# Part3.net
KiCad netlist of a schematic drawn in Altium Designer
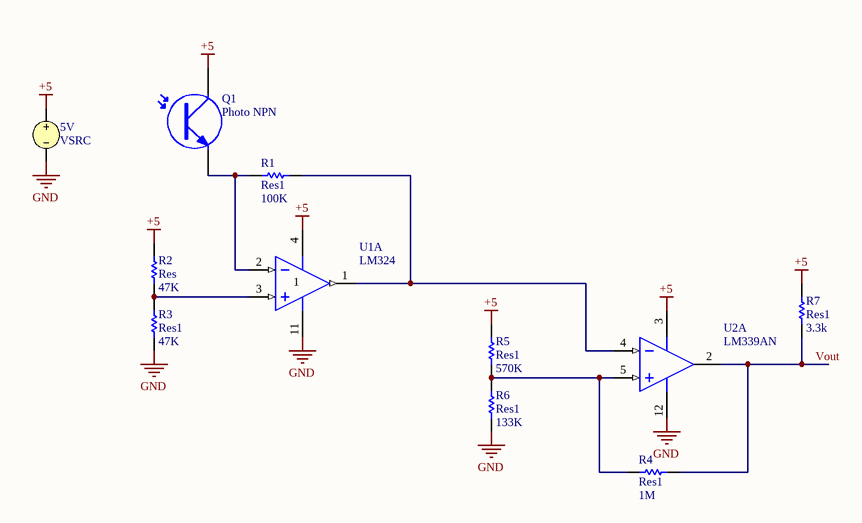
[diagram p0: Part3.SchDoc]

(export (version "E")
  (design (tool "Eeschema 10.0.6"))
  (components
    (comp (ref "5V")
      (value "VSRC")
      (description "Voltage Source")
      (fields (field (name "PUBLISHER") "Altium Limited"))
      (libsource (lib "Simulation Sources") (part "VSRC"))
    )
    (comp (ref "Q1")
      (value "Photo NPN")
      (footprint "SFM-T2(3)/X1.6V")
      (description "NPN Phototransistor")
      (fields (field (name "MANUFACTURER") "Generic Components"))
      (libsource (lib "ME218_BaseLib") (part "Photo NPN"))
    )
    (comp (ref "R1")
      (value "Res1")
      (footprint "AXIAL-0.3")
      (description "Resistor")
      (fields
        (field (name "MANUFACTURER") "Generic Components")
        (field (name "ALTIUM_VALUE") "100K")
        (field (name "PUBLISHER") "Altium Hobart Technology Centre")
      )
      (libsource (lib "ME218_BaseLib") (part "Res1"))
    )
    (comp (ref "R2")
      (value "Res")
      (footprint "AXIAL-0.3")
      (description "Resistor")
      (fields
        (field (name "MANUFACTURER") "Generic Components")
        (field (name "ALTIUM_VALUE") "47K")
        (field (name "PUBLISHER") "Altium Hobart Technology Centre")
      )
      (libsource (lib "ME218_BaseLib") (part "Res1"))
    )
    (comp (ref "R3")
      (value "Res1")
      (footprint "AXIAL-0.3")
      (description "Resistor")
      (fields
        (field (name "MANUFACTURER") "Generic Components")
        (field (name "ALTIUM_VALUE") "47K")
        (field (name "PUBLISHER") "Altium Hobart Technology Centre")
      )
      (libsource (lib "ME218_BaseLib") (part "Res1"))
    )
    (comp (ref "R4")
      (value "Res1")
      (footprint "AXIAL-0.3")
      (description "Resistor")
      (fields
        (field (name "MANUFACTURER") "Generic Components")
        (field (name "ALTIUM_VALUE") "1M")
        (field (name "PUBLISHER") "Altium Hobart Technology Centre")
      )
      (libsource (lib "ME218_BaseLib") (part "Res1"))
    )
    (comp (ref "R5")
      (value "Res1")
      (footprint "AXIAL-0.3")
      (description "Resistor")
      (fields
        (field (name "MANUFACTURER") "Generic Components")
        (field (name "ALTIUM_VALUE") "570K")
        (field (name "PUBLISHER") "Altium Hobart Technology Centre")
      )
      (libsource (lib "ME218_BaseLib") (part "Res1"))
    )
    (comp (ref "R6")
      (value "Res1")
      (footprint "AXIAL-0.3")
      (description "Resistor")
      (fields
        (field (name "MANUFACTURER") "Generic Components")
        (field (name "ALTIUM_VALUE") "133K")
        (field (name "PUBLISHER") "Altium Hobart Technology Centre")
      )
      (libsource (lib "ME218_BaseLib") (part "Res1"))
    )
    (comp (ref "R7")
      (value "Res1")
      (footprint "AXIAL-0.3")
      (description "Resistor")
      (fields
        (field (name "MANUFACTURER") "Generic Components")
        (field (name "ALTIUM_VALUE") "3.3k")
        (field (name "PUBLISHER") "Altium Hobart Technology Centre")
      )
      (libsource (lib "ME218_BaseLib") (part "Res1"))
    )
    (comp (ref "U1")
      (value "LM324")
      (footprint "DIP-14")
      (description "Low-Power Quad Operational Amplifier")
      (fields
        (field (name "MANUFACTURER") "National Semiconductor")
        (field (name "PUBLISHER") "Altium Hobart Technology Centre")
      )
      (libsource (lib "ME218_BaseLib") (part "LM324AJ"))
    )
    (comp (ref "U2")
      (value "LM339AN")
      (footprint "DIP-14/D19.7")
      (description "Quad Single-Supply Comparator")
      (fields
        (field (name "MANUFACTURER") "Motorola")
        (field (name "PUBLISHER") "Altium Hobart Technology Centre")
      )
      (libsource (lib "ME218_BaseLib") (part "LM339AN"))
    )
  )
  (nets
    (net (code "1") (name "+5") (class "Default")
      (node (ref "5V") (pin "1") (pinfunction "1_1") (pintype "passive"))
      (node (ref "Q1") (pin "1") (pinfunction "C_1") (pintype "passive"))
      (node (ref "R2") (pin "1") (pinfunction "1_1") (pintype "passive"))
      (node (ref "R5") (pin "2") (pinfunction "2_2") (pintype "passive"))
      (node (ref "R7") (pin "2") (pinfunction "2_2") (pintype "passive"))
      (node (ref "U1") (pin "4") (pinfunction "V+_4") (pintype "power_in"))
      (node (ref "U2") (pin "3") (pinfunction "V+_3") (pintype "power_in"))
    )
    (net (code "2") (name "/Vout") (class "Default")
      (node (ref "R4") (pin "2") (pinfunction "2_2") (pintype "passive"))
      (node (ref "R7") (pin "1") (pinfunction "1_1") (pintype "passive"))
      (node (ref "U2") (pin "2") (pinfunction "OUT_2") (pintype "open_collector"))
    )
    (net (code "3") (name "GND") (class "Default")
      (node (ref "5V") (pin "2") (pinfunction "2_2") (pintype "passive"))
      (node (ref "R3") (pin "2") (pinfunction "2_2") (pintype "passive"))
      (node (ref "R6") (pin "1") (pinfunction "1_1") (pintype "passive"))
      (node (ref "U1") (pin "11") (pinfunction "GND_11") (pintype "power_in"))
      (node (ref "U2") (pin "12") (pinfunction "GND_12") (pintype "power_in"))
    )
    (net (code "4") (name "Net-(Q1-E)") (class "Default")
      (node (ref "Q1") (pin "3") (pinfunction "E_3") (pintype "passive"))
      (node (ref "R1") (pin "2") (pinfunction "2_2") (pintype "passive"))
      (node (ref "U1") (pin "2") (pinfunction "IN-_2") (pintype "input"))
    )
    (net (code "5") (name "Net-(U1A-IN+)") (class "Default")
      (node (ref "R2") (pin "2") (pinfunction "2_2") (pintype "passive"))
      (node (ref "R3") (pin "1") (pinfunction "1_1") (pintype "passive"))
      (node (ref "U1") (pin "3") (pinfunction "IN+_3") (pintype "input"))
    )
    (net (code "6") (name "Net-(U1A-OUT)") (class "Default")
      (node (ref "R1") (pin "1") (pinfunction "1_1") (pintype "passive"))
      (node (ref "U1") (pin "1") (pinfunction "OUT_1") (pintype "output"))
      (node (ref "U2") (pin "4") (pinfunction "IN-_4") (pintype "input"))
    )
    (net (code "7") (name "Net-(U2A-IN+)") (class "Default")
      (node (ref "R4") (pin "1") (pinfunction "1_1") (pintype "passive"))
      (node (ref "R5") (pin "1") (pinfunction "1_1") (pintype "passive"))
      (node (ref "R6") (pin "2") (pinfunction "2_2") (pintype "passive"))
      (node (ref "U2") (pin "5") (pinfunction "IN+_5") (pintype "input"))
    )
  )
)
